# HV_Vector_Board.net
KiCad netlist of a schematic drawn in EAGLE
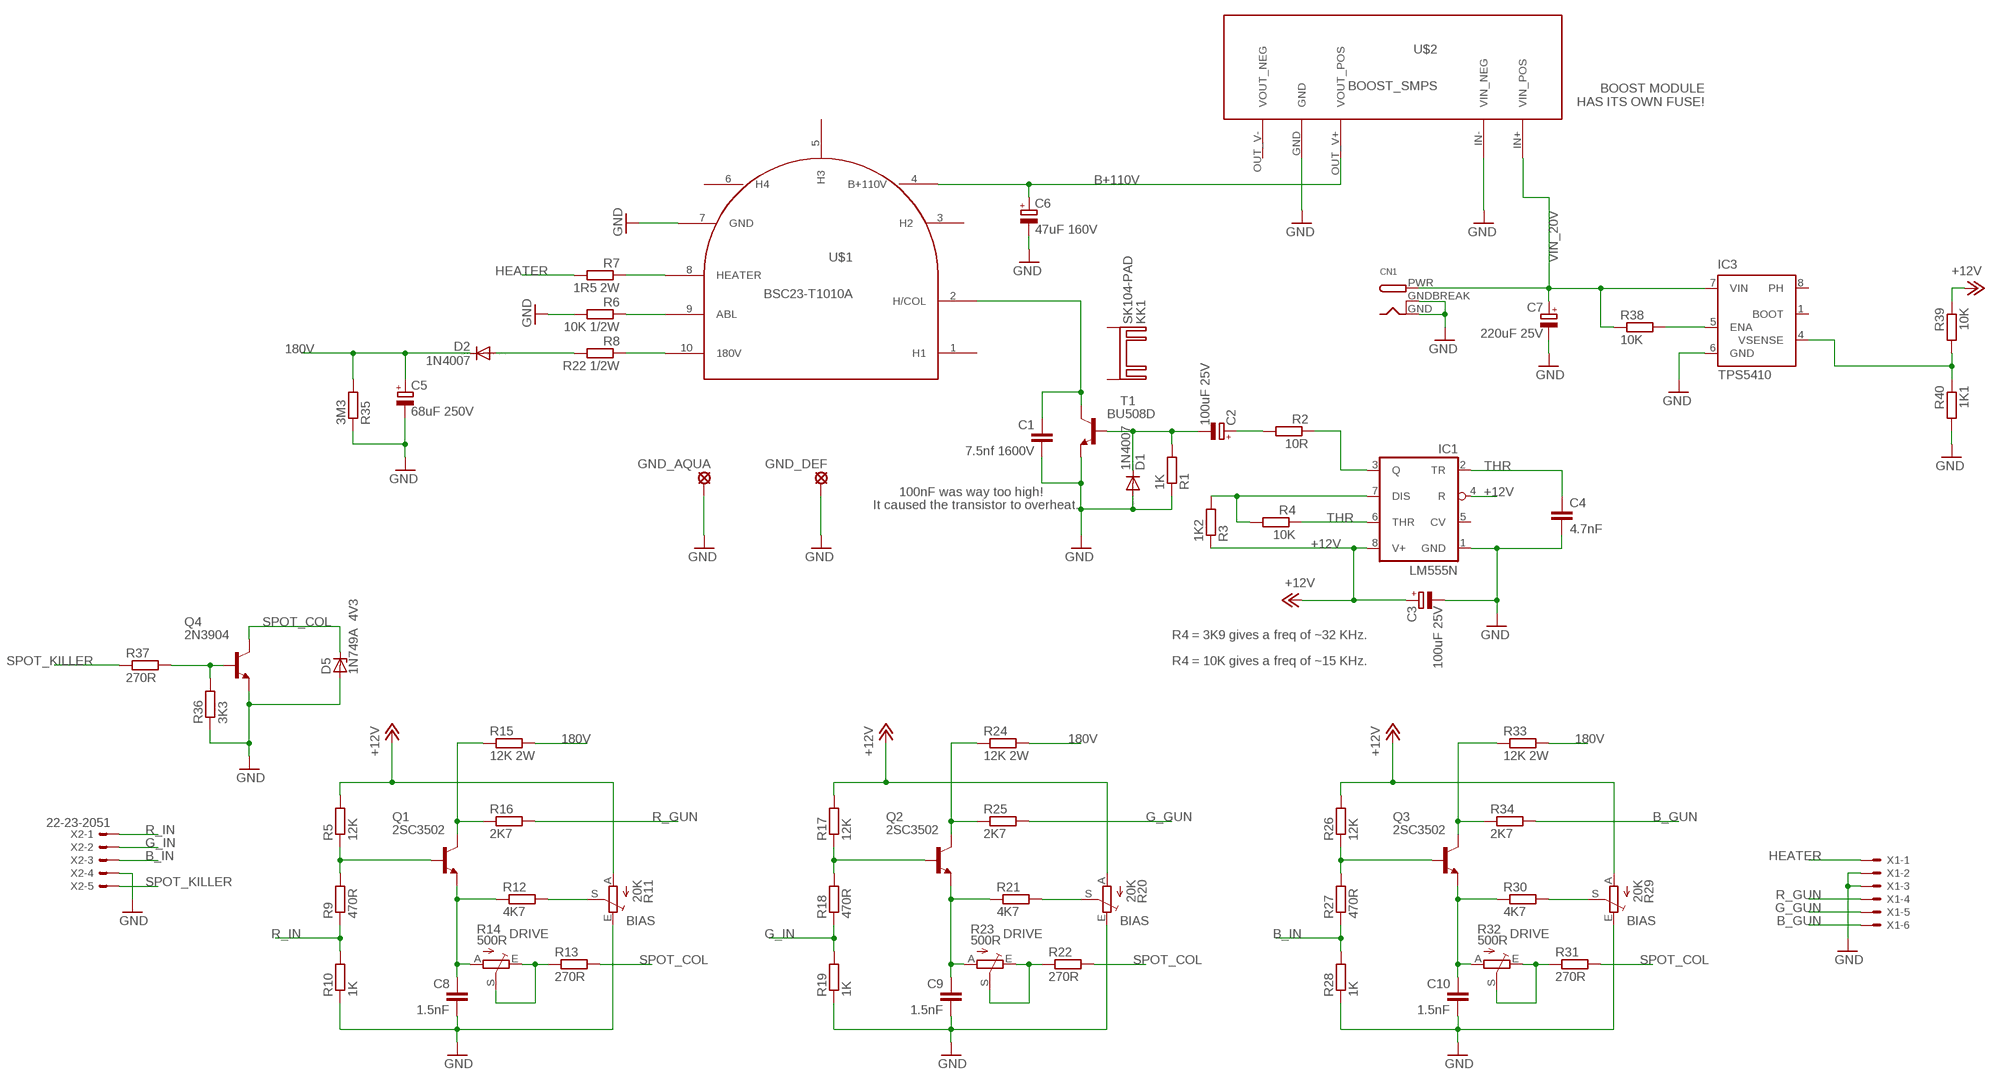
[diagram p0: schematic, sheet 1]

(export (version "E")
  (design (tool "Eeschema 10.0.6"))
  (components
    (comp (ref "C1")
      (value "7.5nf 1600V")
      (footprint "eagle-import:C075-052X106")
      (libsource (lib "eagle-import") (part "C-EU075-052X106"))
    )
    (comp (ref "C2")
      (value "100uF 25V")
      (footprint "eagle-import:E2-5")
      (libsource (lib "eagle-import") (part "CPOL-EUE2-5"))
    )
    (comp (ref "C3")
      (value "100uF 25V")
      (footprint "eagle-import:E2-5")
      (libsource (lib "eagle-import") (part "CPOL-EUE2-5"))
    )
    (comp (ref "C4")
      (value "4.7nF")
      (footprint "eagle-import:C025-025X050")
      (libsource (lib "eagle-import") (part "C-EU025-025X050"))
    )
    (comp (ref "C5")
      (value "68uF 250V")
      (footprint "eagle-import:E5-8,5")
      (libsource (lib "eagle-import") (part "CPOL-EUE5-8.5"))
    )
    (comp (ref "C6")
      (value "47uF 160V")
      (footprint "eagle-import:E3,5-8")
      (libsource (lib "eagle-import") (part "CPOL-EUE3.5-8"))
    )
    (comp (ref "C7")
      (value "220uF 25V")
      (footprint "eagle-import:E5-8,5")
      (libsource (lib "eagle-import") (part "CPOL-EUE5-8.5"))
    )
    (comp (ref "C8")
      (value "1.5nF")
      (footprint "eagle-import:C025-025X050")
      (libsource (lib "eagle-import") (part "C-EU025-025X050"))
    )
    (comp (ref "C9")
      (value "1.5nF")
      (footprint "eagle-import:C025-025X050")
      (libsource (lib "eagle-import") (part "C-EU025-025X050"))
    )
    (comp (ref "C10")
      (value "1.5nF")
      (footprint "eagle-import:C025-025X050")
      (libsource (lib "eagle-import") (part "C-EU025-025X050"))
    )
    (comp (ref "CN1")
      (value "DCBARRELPTH")
      (footprint "eagle-import:DCJACK_2MM_PTH")
      (libsource (lib "eagle-import") (part "DCBARRELPTH"))
    )
    (comp (ref "D1")
      (value "1N4007")
      (footprint "eagle-import:DO41-10")
      (libsource (lib "eagle-import") (part "1N4004"))
    )
    (comp (ref "D2")
      (value "1N4007")
      (footprint "eagle-import:DO41-10")
      (libsource (lib "eagle-import") (part "1N4004"))
    )
    (comp (ref "D5")
      (value "1N749A 4V3")
      (footprint "eagle-import:ZDIO-7.5")
      (libsource (lib "eagle-import") (part "ZENER-DIODEZD-7.5"))
    )
    (comp (ref "GND_AQUA")
      (value "SE14")
      (footprint "eagle-import:SE14")
      (libsource (lib "eagle-import") (part "SE14"))
    )
    (comp (ref "GND_DEF")
      (value "SE14")
      (footprint "eagle-import:SE14")
      (libsource (lib "eagle-import") (part "SE14"))
    )
    (comp (ref "IC1")
      (value "LM555N")
      (footprint "eagle-import:DIL08")
      (libsource (lib "eagle-import") (part "555NLM"))
    )
    (comp (ref "IC3")
      (value "TPS5410")
      (footprint "eagle-import:D_R-PDSO-G08")
      (fields (field (name "MPN") "TPS5410DR"))
      (libsource (lib "eagle-import") (part "TPS5410"))
    )
    (comp (ref "KK1")
      (value "SK104-PAD")
      (footprint "eagle-import:SK104-PAD")
      (libsource (lib "eagle-import") (part "SK104-PAD"))
    )
    (comp (ref "Q1")
      (value "2SC3502")
      (footprint "eagle-import:TO126")
      (libsource (lib "eagle-import") (part "2N4923"))
    )
    (comp (ref "Q2")
      (value "2SC3502")
      (footprint "eagle-import:TO126")
      (libsource (lib "eagle-import") (part "2N4923"))
    )
    (comp (ref "Q3")
      (value "2SC3502")
      (footprint "eagle-import:TO126")
      (libsource (lib "eagle-import") (part "2N4923"))
    )
    (comp (ref "Q4")
      (value "2N3904")
      (footprint "eagle-import:TO92")
      (libsource (lib "eagle-import") (part "2N3904"))
    )
    (comp (ref "R1")
      (value "1K")
      (footprint "eagle-import:0207_10")
      (libsource (lib "eagle-import") (part "R-EU_0207/10"))
    )
    (comp (ref "R2")
      (value "10R")
      (footprint "eagle-import:0204_7")
      (libsource (lib "eagle-import") (part "R-EU_0204/7"))
    )
    (comp (ref "R3")
      (value "1K2")
      (footprint "eagle-import:0204_7")
      (libsource (lib "eagle-import") (part "R-EU_0204/7"))
    )
    (comp (ref "R4")
      (value "10K")
      (footprint "eagle-import:0204_7")
      (libsource (lib "eagle-import") (part "R-EU_0204/7"))
    )
    (comp (ref "R5")
      (value "12K")
      (footprint "eagle-import:0204_7")
      (libsource (lib "eagle-import") (part "R-EU_0204/7"))
    )
    (comp (ref "R6")
      (value "10K 1/2W")
      (footprint "eagle-import:0207_10")
      (libsource (lib "eagle-import") (part "R-EU_0207/10"))
    )
    (comp (ref "R7")
      (value "1R5 2W")
      (footprint "eagle-import:0309_12")
      (libsource (lib "eagle-import") (part "R-EU_0309/12"))
    )
    (comp (ref "R8")
      (value "R22 1/2W")
      (footprint "eagle-import:0204_7")
      (libsource (lib "eagle-import") (part "R-EU_0204/7"))
    )
    (comp (ref "R9")
      (value "470R")
      (footprint "eagle-import:0204_7")
      (libsource (lib "eagle-import") (part "R-EU_0204/7"))
    )
    (comp (ref "R10")
      (value "1K")
      (footprint "eagle-import:0204_7")
      (libsource (lib "eagle-import") (part "R-EU_0204/7"))
    )
    (comp (ref "R11")
      (value "20K")
      (footprint "eagle-import:RS3")
      (libsource (lib "eagle-import") (part "TRIM_EU-RS3"))
    )
    (comp (ref "R12")
      (value "4K7")
      (footprint "eagle-import:0204_7")
      (libsource (lib "eagle-import") (part "R-EU_0204/7"))
    )
    (comp (ref "R13")
      (value "270R")
      (footprint "eagle-import:0204_7")
      (libsource (lib "eagle-import") (part "R-EU_0204/7"))
    )
    (comp (ref "R14")
      (value "500R")
      (footprint "eagle-import:RS3")
      (libsource (lib "eagle-import") (part "TRIM_EU-RS3"))
    )
    (comp (ref "R15")
      (value "12K 2W")
      (footprint "eagle-import:0309_12")
      (libsource (lib "eagle-import") (part "R-EU_0309/12"))
    )
    (comp (ref "R16")
      (value "2K7")
      (footprint "eagle-import:0204_7")
      (libsource (lib "eagle-import") (part "R-EU_0204/7"))
    )
    (comp (ref "R17")
      (value "12K")
      (footprint "eagle-import:0204_7")
      (libsource (lib "eagle-import") (part "R-EU_0204/7"))
    )
    (comp (ref "R18")
      (value "470R")
      (footprint "eagle-import:0204_7")
      (libsource (lib "eagle-import") (part "R-EU_0204/7"))
    )
    (comp (ref "R19")
      (value "1K")
      (footprint "eagle-import:0204_7")
      (libsource (lib "eagle-import") (part "R-EU_0204/7"))
    )
    (comp (ref "R20")
      (value "20K")
      (footprint "eagle-import:RS3")
      (libsource (lib "eagle-import") (part "TRIM_EU-RS3"))
    )
    (comp (ref "R21")
      (value "4K7")
      (footprint "eagle-import:0204_7")
      (libsource (lib "eagle-import") (part "R-EU_0204/7"))
    )
    (comp (ref "R22")
      (value "270R")
      (footprint "eagle-import:0204_7")
      (libsource (lib "eagle-import") (part "R-EU_0204/7"))
    )
    (comp (ref "R23")
      (value "500R")
      (footprint "eagle-import:RS3")
      (libsource (lib "eagle-import") (part "TRIM_EU-RS3"))
    )
    (comp (ref "R24")
      (value "12K 2W")
      (footprint "eagle-import:0309_12")
      (libsource (lib "eagle-import") (part "R-EU_0309/12"))
    )
    (comp (ref "R25")
      (value "2K7")
      (footprint "eagle-import:0204_7")
      (libsource (lib "eagle-import") (part "R-EU_0204/7"))
    )
    (comp (ref "R26")
      (value "12K")
      (footprint "eagle-import:0204_7")
      (libsource (lib "eagle-import") (part "R-EU_0204/7"))
    )
    (comp (ref "R27")
      (value "470R")
      (footprint "eagle-import:0204_7")
      (libsource (lib "eagle-import") (part "R-EU_0204/7"))
    )
    (comp (ref "R28")
      (value "1K")
      (footprint "eagle-import:0204_7")
      (libsource (lib "eagle-import") (part "R-EU_0204/7"))
    )
    (comp (ref "R29")
      (value "20K")
      (footprint "eagle-import:RS3")
      (libsource (lib "eagle-import") (part "TRIM_EU-RS3"))
    )
    (comp (ref "R30")
      (value "4K7")
      (footprint "eagle-import:0204_7")
      (libsource (lib "eagle-import") (part "R-EU_0204/7"))
    )
    (comp (ref "R31")
      (value "270R")
      (footprint "eagle-import:0204_7")
      (libsource (lib "eagle-import") (part "R-EU_0204/7"))
    )
    (comp (ref "R32")
      (value "500R")
      (footprint "eagle-import:RS3")
      (libsource (lib "eagle-import") (part "TRIM_EU-RS3"))
    )
    (comp (ref "R33")
      (value "12K 2W")
      (footprint "eagle-import:0309_12")
      (libsource (lib "eagle-import") (part "R-EU_0309/12"))
    )
    (comp (ref "R34")
      (value "2K7")
      (footprint "eagle-import:0204_7")
      (libsource (lib "eagle-import") (part "R-EU_0204/7"))
    )
    (comp (ref "R35")
      (value "3M3")
      (footprint "eagle-import:0204_7")
      (libsource (lib "eagle-import") (part "R-EU_0204/7"))
    )
    (comp (ref "R36")
      (value "3K3")
      (footprint "eagle-import:0204_7")
      (libsource (lib "eagle-import") (part "R-EU_0204/7"))
    )
    (comp (ref "R37")
      (value "270R")
      (footprint "eagle-import:0204_7")
      (libsource (lib "eagle-import") (part "R-EU_0204/7"))
    )
    (comp (ref "R38")
      (value "10K")
      (footprint "eagle-import:0204_7")
      (libsource (lib "eagle-import") (part "R-EU_0204/7"))
    )
    (comp (ref "R39")
      (value "10K")
      (footprint "eagle-import:0204_7")
      (libsource (lib "eagle-import") (part "R-EU_0204/7"))
    )
    (comp (ref "R40")
      (value "1K1")
      (footprint "eagle-import:0204_7")
      (libsource (lib "eagle-import") (part "R-EU_0204/7"))
    )
    (comp (ref "T1")
      (value "BU508D")
      (footprint "eagle-import:TO218V")
      (libsource (lib "eagle-import") (part "-NPN-TO218V"))
    )
    (comp (ref "U$1")
      (value "BSC23-T1010A")
      (footprint "eagle-import:BSC25_FLYBACK")
      (libsource (lib "eagle-import") (part "BSC23-T1010A"))
    )
    (comp (ref "U$2")
      (value "BOOST_SMPS")
      (footprint "eagle-import:BOOST_PSU")
      (libsource (lib "eagle-import") (part "BOOST_SMPS"))
    )
    (comp (ref "X1")
      (value "22-23-2061")
      (footprint "eagle-import:22-23-2061")
      (fields (field (name "MF") "MOLEX"))
      (libsource (lib "eagle-import") (part "22-23-2061"))
    )
    (comp (ref "X2")
      (value "22-23-2051")
      (footprint "eagle-import:22-23-2051")
      (fields (field (name "MF") "MOLEX"))
      (libsource (lib "eagle-import") (part "22-23-2051"))
    )
  )
  (nets
    (net (code "1") (name "+12V") (class "Default")
      (node (ref "C3") (pin "+") (pinfunction "+_+") (pintype "passive"))
      (node (ref "IC1") (pin "4") (pinfunction "R_4") (pintype "input"))
      (node (ref "IC1") (pin "8") (pinfunction "V+_8") (pintype "power_in"))
      (node (ref "R11") (pin "A") (pinfunction "A_A") (pintype "passive"))
      (node (ref "R17") (pin "2") (pinfunction "2_2") (pintype "passive"))
      (node (ref "R20") (pin "A") (pinfunction "A_A") (pintype "passive"))
      (node (ref "R26") (pin "2") (pinfunction "2_2") (pintype "passive"))
      (node (ref "R29") (pin "A") (pinfunction "A_A") (pintype "passive"))
      (node (ref "R3") (pin "1") (pinfunction "1_1") (pintype "passive"))
      (node (ref "R39") (pin "1") (pinfunction "1_1") (pintype "passive"))
      (node (ref "R5") (pin "2") (pinfunction "2_2") (pintype "passive"))
    )
    (net (code "2") (name "/180V") (class "Default")
      (node (ref "C5") (pin "+") (pinfunction "+_+") (pintype "passive"))
      (node (ref "D2") (pin "C") (pinfunction "C_C") (pintype "passive"))
      (node (ref "R15") (pin "2") (pinfunction "2_2") (pintype "passive"))
      (node (ref "R24") (pin "2") (pinfunction "2_2") (pintype "passive"))
      (node (ref "R33") (pin "2") (pinfunction "2_2") (pintype "passive"))
      (node (ref "R35") (pin "2") (pinfunction "2_2") (pintype "passive"))
    )
    (net (code "3") (name "/B+110V") (class "Default")
      (node (ref "C6") (pin "+") (pinfunction "+_+") (pintype "passive"))
      (node (ref "U$1") (pin "4") (pinfunction "B+110V_4") (pintype "bidirectional"))
      (node (ref "U$2") (pin "OUT_V+") (pinfunction "VOUT_POS_OUT_V+") (pintype "bidirectional"))
    )
    (net (code "4") (name "/B_GUN") (class "Default")
      (node (ref "R34") (pin "2") (pinfunction "2_2") (pintype "passive"))
      (node (ref "X1") (pin "6") (pinfunction "S_6") (pintype "passive"))
    )
    (net (code "5") (name "/B_IN") (class "Default")
      (node (ref "R27") (pin "1") (pinfunction "1_1") (pintype "passive"))
      (node (ref "R28") (pin "2") (pinfunction "2_2") (pintype "passive"))
      (node (ref "X2") (pin "3") (pinfunction "S_3") (pintype "passive"))
    )
    (net (code "6") (name "/G_GUN") (class "Default")
      (node (ref "R25") (pin "2") (pinfunction "2_2") (pintype "passive"))
      (node (ref "X1") (pin "5") (pinfunction "S_5") (pintype "passive"))
    )
    (net (code "7") (name "/G_IN") (class "Default")
      (node (ref "R18") (pin "1") (pinfunction "1_1") (pintype "passive"))
      (node (ref "R19") (pin "2") (pinfunction "2_2") (pintype "passive"))
      (node (ref "X2") (pin "2") (pinfunction "S_2") (pintype "passive"))
    )
    (net (code "8") (name "/HEATER") (class "Default")
      (node (ref "R7") (pin "2") (pinfunction "2_2") (pintype "passive"))
      (node (ref "X1") (pin "1") (pinfunction "S_1") (pintype "passive"))
    )
    (net (code "9") (name "/R_GUN") (class "Default")
      (node (ref "R16") (pin "2") (pinfunction "2_2") (pintype "passive"))
      (node (ref "X1") (pin "4") (pinfunction "S_4") (pintype "passive"))
    )
    (net (code "10") (name "/R_IN") (class "Default")
      (node (ref "R10") (pin "2") (pinfunction "2_2") (pintype "passive"))
      (node (ref "R9") (pin "1") (pinfunction "1_1") (pintype "passive"))
      (node (ref "X2") (pin "1") (pinfunction "S_1") (pintype "passive"))
    )
    (net (code "11") (name "/SPOT_COL") (class "Default")
      (node (ref "D5") (pin "C") (pinfunction "C_C") (pintype "passive"))
      (node (ref "Q4") (pin "1") (pinfunction "C_1") (pintype "passive"))
      (node (ref "R13") (pin "2") (pinfunction "2_2") (pintype "passive"))
      (node (ref "R22") (pin "2") (pinfunction "2_2") (pintype "passive"))
      (node (ref "R31") (pin "2") (pinfunction "2_2") (pintype "passive"))
    )
    (net (code "12") (name "/SPOT_KILLER") (class "Default")
      (node (ref "R37") (pin "1") (pinfunction "1_1") (pintype "passive"))
      (node (ref "X2") (pin "5") (pinfunction "S_5") (pintype "passive"))
    )
    (net (code "13") (name "/THR") (class "Default")
      (node (ref "C4") (pin "1") (pinfunction "1_1") (pintype "passive"))
      (node (ref "IC1") (pin "2") (pinfunction "TR_2") (pintype "input"))
      (node (ref "IC1") (pin "6") (pinfunction "THR_6") (pintype "input"))
      (node (ref "R4") (pin "1") (pinfunction "1_1") (pintype "passive"))
    )
    (net (code "14") (name "/VIN_20V") (class "Default")
      (node (ref "C7") (pin "+") (pinfunction "+_+") (pintype "passive"))
      (node (ref "CN1") (pin "PWR") (pinfunction "PWR_PWR") (pintype "power_in"))
      (node (ref "IC3") (pin "7") (pinfunction "VIN_7") (pintype "input"))
      (node (ref "R38") (pin "1") (pinfunction "1_1") (pintype "passive"))
      (node (ref "U$2") (pin "IN+") (pinfunction "VIN_POS_IN+") (pintype "bidirectional"))
    )
    (net (code "15") (name "GND") (class "Default")
      (node (ref "C1") (pin "2") (pinfunction "2_2") (pintype "passive"))
      (node (ref "C10") (pin "2") (pinfunction "2_2") (pintype "passive"))
      (node (ref "C3") (pin "-") (pinfunction "-_-") (pintype "passive"))
      (node (ref "C4") (pin "2") (pinfunction "2_2") (pintype "passive"))
      (node (ref "C5") (pin "-") (pinfunction "-_-") (pintype "passive"))
      (node (ref "C6") (pin "-") (pinfunction "-_-") (pintype "passive"))
      (node (ref "C7") (pin "-") (pinfunction "-_-") (pintype "passive"))
      (node (ref "C8") (pin "2") (pinfunction "2_2") (pintype "passive"))
      (node (ref "C9") (pin "2") (pinfunction "2_2") (pintype "passive"))
      (node (ref "CN1") (pin "GND") (pinfunction "GND_GND") (pintype "power_in"))
      (node (ref "CN1") (pin "GNDBREAK") (pinfunction "GNDBREAK_GNDBREAK") (pintype "power_in"))
      (node (ref "D1") (pin "A") (pinfunction "A_A") (pintype "passive"))
      (node (ref "D5") (pin "A") (pinfunction "A_A") (pintype "passive"))
      (node (ref "GND_AQUA") (pin "MP") (pinfunction "MP_MP") (pintype "passive"))
      (node (ref "GND_DEF") (pin "MP") (pinfunction "MP_MP") (pintype "passive"))
      (node (ref "IC1") (pin "1") (pinfunction "GND_1") (pintype "power_in"))
      (node (ref "IC3") (pin "6") (pinfunction "GND_6") (pintype "power_in"))
      (node (ref "Q4") (pin "3") (pinfunction "E_3") (pintype "passive"))
      (node (ref "R1") (pin "1") (pinfunction "1_1") (pintype "passive"))
      (node (ref "R10") (pin "1") (pinfunction "1_1") (pintype "passive"))
      (node (ref "R11") (pin "E") (pinfunction "E_E") (pintype "passive"))
      (node (ref "R19") (pin "1") (pinfunction "1_1") (pintype "passive"))
      (node (ref "R20") (pin "E") (pinfunction "E_E") (pintype "passive"))
      (node (ref "R28") (pin "1") (pinfunction "1_1") (pintype "passive"))
      (node (ref "R29") (pin "E") (pinfunction "E_E") (pintype "passive"))
      (node (ref "R35") (pin "1") (pinfunction "1_1") (pintype "passive"))
      (node (ref "R36") (pin "1") (pinfunction "1_1") (pintype "passive"))
      (node (ref "R40") (pin "2") (pinfunction "2_2") (pintype "passive"))
      (node (ref "R6") (pin "2") (pinfunction "2_2") (pintype "passive"))
      (node (ref "T1") (pin "3") (pinfunction "E_3") (pintype "passive"))
      (node (ref "U$1") (pin "7") (pinfunction "GND_7") (pintype "bidirectional"))
      (node (ref "U$2") (pin "GND") (pinfunction "GND_GND") (pintype "bidirectional"))
      (node (ref "U$2") (pin "IN-") (pinfunction "VIN_NEG_IN-") (pintype "bidirectional"))
      (node (ref "X1") (pin "2") (pinfunction "S_2") (pintype "passive"))
      (node (ref "X1") (pin "3") (pinfunction "S_3") (pintype "passive"))
      (node (ref "X2") (pin "4") (pinfunction "S_4") (pintype "passive"))
    )
    (net (code "16") (name "Net-(C2-Pad+)") (class "Default")
      (node (ref "C2") (pin "+") (pinfunction "+_+") (pintype "passive"))
      (node (ref "R2") (pin "2") (pinfunction "2_2") (pintype "passive"))
    )
    (net (code "17") (name "Net-(D2-PadA)") (class "Default")
      (node (ref "D2") (pin "A") (pinfunction "A_A") (pintype "passive"))
      (node (ref "R8") (pin "2") (pinfunction "2_2") (pintype "passive"))
    )
    (net (code "18") (name "Net-(IC1-DIS)") (class "Default")
      (node (ref "IC1") (pin "7") (pinfunction "DIS_7") (pintype "input"))
      (node (ref "R3") (pin "2") (pinfunction "2_2") (pintype "passive"))
      (node (ref "R4") (pin "2") (pinfunction "2_2") (pintype "passive"))
    )
    (net (code "19") (name "Net-(IC1-Q)") (class "Default")
      (node (ref "IC1") (pin "3") (pinfunction "Q_3") (pintype "output"))
      (node (ref "R2") (pin "1") (pinfunction "1_1") (pintype "passive"))
    )
    (net (code "20") (name "Net-(IC3-ENA)") (class "Default")
      (node (ref "IC3") (pin "5") (pinfunction "ENA_5") (pintype "input"))
      (node (ref "R38") (pin "2") (pinfunction "2_2") (pintype "passive"))
    )
    (net (code "21") (name "Net-(IC3-VSENSE)") (class "Default")
      (node (ref "IC3") (pin "4") (pinfunction "VSENSE_4") (pintype "input"))
      (node (ref "R39") (pin "2") (pinfunction "2_2") (pintype "passive"))
      (node (ref "R40") (pin "1") (pinfunction "1_1") (pintype "passive"))
    )
    (net (code "22") (name "Net-(Q1-B)") (class "Default")
      (node (ref "Q1") (pin "3") (pinfunction "B_3") (pintype "passive"))
      (node (ref "R5") (pin "1") (pinfunction "1_1") (pintype "passive"))
      (node (ref "R9") (pin "2") (pinfunction "2_2") (pintype "passive"))
    )
    (net (code "23") (name "Net-(Q1-C)") (class "Default")
      (node (ref "Q1") (pin "2") (pinfunction "C_2") (pintype "passive"))
      (node (ref "R15") (pin "1") (pinfunction "1_1") (pintype "passive"))
      (node (ref "R16") (pin "1") (pinfunction "1_1") (pintype "passive"))
    )
    (net (code "24") (name "Net-(Q1-E)") (class "Default")
      (node (ref "C8") (pin "1") (pinfunction "1_1") (pintype "passive"))
      (node (ref "Q1") (pin "1") (pinfunction "E_1") (pintype "passive"))
      (node (ref "R12") (pin "1") (pinfunction "1_1") (pintype "passive"))
      (node (ref "R14") (pin "A") (pinfunction "A_A") (pintype "passive"))
    )
    (net (code "25") (name "Net-(Q2-B)") (class "Default")
      (node (ref "Q2") (pin "3") (pinfunction "B_3") (pintype "passive"))
      (node (ref "R17") (pin "1") (pinfunction "1_1") (pintype "passive"))
      (node (ref "R18") (pin "2") (pinfunction "2_2") (pintype "passive"))
    )
    (net (code "26") (name "Net-(Q2-C)") (class "Default")
      (node (ref "Q2") (pin "2") (pinfunction "C_2") (pintype "passive"))
      (node (ref "R24") (pin "1") (pinfunction "1_1") (pintype "passive"))
      (node (ref "R25") (pin "1") (pinfunction "1_1") (pintype "passive"))
    )
    (net (code "27") (name "Net-(Q2-E)") (class "Default")
      (node (ref "C9") (pin "1") (pinfunction "1_1") (pintype "passive"))
      (node (ref "Q2") (pin "1") (pinfunction "E_1") (pintype "passive"))
      (node (ref "R21") (pin "1") (pinfunction "1_1") (pintype "passive"))
      (node (ref "R23") (pin "A") (pinfunction "A_A") (pintype "passive"))
    )
    (net (code "28") (name "Net-(Q3-B)") (class "Default")
      (node (ref "Q3") (pin "3") (pinfunction "B_3") (pintype "passive"))
      (node (ref "R26") (pin "1") (pinfunction "1_1") (pintype "passive"))
      (node (ref "R27") (pin "2") (pinfunction "2_2") (pintype "passive"))
    )
    (net (code "29") (name "Net-(Q3-C)") (class "Default")
      (node (ref "Q3") (pin "2") (pinfunction "C_2") (pintype "passive"))
      (node (ref "R33") (pin "1") (pinfunction "1_1") (pintype "passive"))
      (node (ref "R34") (pin "1") (pinfunction "1_1") (pintype "passive"))
    )
    (net (code "30") (name "Net-(Q3-E)") (class "Default")
      (node (ref "C10") (pin "1") (pinfunction "1_1") (pintype "passive"))
      (node (ref "Q3") (pin "1") (pinfunction "E_1") (pintype "passive"))
      (node (ref "R30") (pin "1") (pinfunction "1_1") (pintype "passive"))
      (node (ref "R32") (pin "A") (pinfunction "A_A") (pintype "passive"))
    )
    (net (code "31") (name "Net-(Q4-B)") (class "Default")
      (node (ref "Q4") (pin "2") (pinfunction "B_2") (pintype "passive"))
      (node (ref "R36") (pin "2") (pinfunction "2_2") (pintype "passive"))
      (node (ref "R37") (pin "2") (pinfunction "2_2") (pintype "passive"))
    )
    (net (code "32") (name "Net-(R11-PadS)") (class "Default")
      (node (ref "R11") (pin "S") (pinfunction "S_S") (pintype "passive"))
      (node (ref "R12") (pin "2") (pinfunction "2_2") (pintype "passive"))
    )
    (net (code "33") (name "Net-(R13-Pad1)") (class "Default")
      (node (ref "R13") (pin "1") (pinfunction "1_1") (pintype "passive"))
      (node (ref "R14") (pin "E") (pinfunction "E_E") (pintype "passive"))
      (node (ref "R14") (pin "S") (pinfunction "S_S") (pintype "passive"))
    )
    (net (code "34") (name "Net-(R20-PadS)") (class "Default")
      (node (ref "R20") (pin "S") (pinfunction "S_S") (pintype "passive"))
      (node (ref "R21") (pin "2") (pinfunction "2_2") (pintype "passive"))
    )
    (net (code "35") (name "Net-(R22-Pad1)") (class "Default")
      (node (ref "R22") (pin "1") (pinfunction "1_1") (pintype "passive"))
      (node (ref "R23") (pin "E") (pinfunction "E_E") (pintype "passive"))
      (node (ref "R23") (pin "S") (pinfunction "S_S") (pintype "passive"))
    )
    (net (code "36") (name "Net-(R29-PadS)") (class "Default")
      (node (ref "R29") (pin "S") (pinfunction "S_S") (pintype "passive"))
      (node (ref "R30") (pin "2") (pinfunction "2_2") (pintype "passive"))
    )
    (net (code "37") (name "Net-(R31-Pad1)") (class "Default")
      (node (ref "R31") (pin "1") (pinfunction "1_1") (pintype "passive"))
      (node (ref "R32") (pin "E") (pinfunction "E_E") (pintype "passive"))
      (node (ref "R32") (pin "S") (pinfunction "S_S") (pintype "passive"))
    )
    (net (code "38") (name "Net-(T1-B)") (class "Default")
      (node (ref "C2") (pin "-") (pinfunction "-_-") (pintype "passive"))
      (node (ref "D1") (pin "C") (pinfunction "C_C") (pintype "passive"))
      (node (ref "R1") (pin "2") (pinfunction "2_2") (pintype "passive"))
      (node (ref "T1") (pin "1") (pinfunction "B_1") (pintype "passive"))
    )
    (net (code "39") (name "Net-(T1-C)") (class "Default")
      (node (ref "C1") (pin "1") (pinfunction "1_1") (pintype "passive"))
      (node (ref "T1") (pin "2") (pinfunction "C_2") (pintype "passive"))
      (node (ref "U$1") (pin "2") (pinfunction "H/COL_2") (pintype "bidirectional"))
    )
    (net (code "40") (name "Net-(U$1-180V)") (class "Default")
      (node (ref "R8") (pin "1") (pinfunction "1_1") (pintype "passive"))
      (node (ref "U$1") (pin "10") (pinfunction "180V_10") (pintype "bidirectional"))
    )
    (net (code "41") (name "Net-(U$1-ABL)") (class "Default")
      (node (ref "R6") (pin "1") (pinfunction "1_1") (pintype "passive"))
      (node (ref "U$1") (pin "9") (pinfunction "ABL_9") (pintype "bidirectional"))
    )
    (net (code "42") (name "Net-(U$1-HEATER)") (class "Default")
      (node (ref "R7") (pin "1") (pinfunction "1_1") (pintype "passive"))
      (node (ref "U$1") (pin "8") (pinfunction "HEATER_8") (pintype "bidirectional"))
    )
    (net (code "43") (name "unconnected-(IC1-CV-Pad5)") (class "Default")
      (node (ref "IC1") (pin "5") (pinfunction "CV_5") (pintype "input"))
    )
    (net (code "44") (name "unconnected-(IC3-BOOT-Pad1)") (class "Default")
      (node (ref "IC3") (pin "1") (pinfunction "BOOT_1") (pintype "output"))
    )
    (net (code "45") (name "unconnected-(IC3-PH-Pad8)") (class "Default")
      (node (ref "IC3") (pin "8") (pinfunction "PH_8") (pintype "output"))
    )
    (net (code "46") (name "unconnected-(KK1-K-PadK1)") (class "Default")
      (node (ref "KK1") (pin "K1") (pinfunction "K_K1") (pintype "passive"))
    )
    (net (code "47") (name "unconnected-(KK1-K-PadK2)") (class "Default")
      (node (ref "KK1") (pin "K2") (pinfunction "K_K2") (pintype "passive"))
    )
    (net (code "48") (name "unconnected-(U$1-H1-Pad1)") (class "Default")
      (node (ref "U$1") (pin "1") (pinfunction "H1_1") (pintype "bidirectional"))
    )
    (net (code "49") (name "unconnected-(U$1-H2-Pad3)") (class "Default")
      (node (ref "U$1") (pin "3") (pinfunction "H2_3") (pintype "bidirectional"))
    )
    (net (code "50") (name "unconnected-(U$1-H3-Pad5)") (class "Default")
      (node (ref "U$1") (pin "5") (pinfunction "H3_5") (pintype "bidirectional"))
    )
    (net (code "51") (name "unconnected-(U$1-H4-Pad6)") (class "Default")
      (node (ref "U$1") (pin "6") (pinfunction "H4_6") (pintype "bidirectional"))
    )
    (net (code "52") (name "unconnected-(U$2-VOUT_NEG-PadOUT_V-)") (class "Default")
      (node (ref "U$2") (pin "OUT_V-") (pinfunction "VOUT_NEG_OUT_V-") (pintype "bidirectional"))
    )
  )
)
